# joystick.net
KiCad netlist of a schematic drawn in Altium Designer
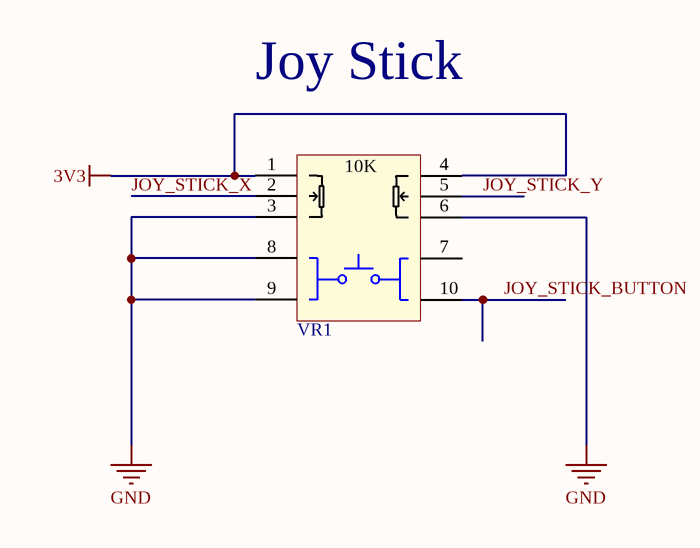
[diagram p0: joystick.SchDoc]

(export (version "E")
  (design (tool "Eeschema 10.0.6"))
  (components
    (comp (ref "VR1")
      (value "Joystick 10k with Sw")
      (footprint "Joystick_Sw")
      (description "JOYSTICK 10K OHM 2 AXIS TH")
      (libsource (lib "ENCE461AD19_19V2") (part "Joystick 10k with Sw"))
    )
  )
  (nets
    (net (code "1") (name "/JOY_STICK_BUTTON") (class "Default")
      (node (ref "VR1") (pin "10") (pinfunction "10_10") (pintype "passive"))
    )
    (net (code "2") (name "/JOY_STICK_X") (class "Default")
      (node (ref "VR1") (pin "2") (pinfunction "2_2") (pintype "passive"))
    )
    (net (code "3") (name "/JOY_STICK_Y") (class "Default")
      (node (ref "VR1") (pin "5") (pinfunction "2'_5") (pintype "passive"))
    )
    (net (code "4") (name "3V3") (class "Default")
      (node (ref "VR1") (pin "1") (pinfunction "1_1") (pintype "passive"))
      (node (ref "VR1") (pin "4") (pinfunction "1'_4") (pintype "passive"))
    )
    (net (code "5") (name "GND") (class "Default")
      (node (ref "VR1") (pin "3") (pinfunction "3_3") (pintype "passive"))
      (node (ref "VR1") (pin "6") (pinfunction "3'_6") (pintype "passive"))
      (node (ref "VR1") (pin "8") (pinfunction "8_8") (pintype "passive"))
      (node (ref "VR1") (pin "9") (pinfunction "9_9") (pintype "passive"))
    )
    (net (code "6") (name "unconnected-(VR1-Pad7)") (class "Default")
      (node (ref "VR1") (pin "7") (pinfunction "7_7") (pintype "passive"))
    )
  )
)
